# adc-power.net
KiCad netlist of a schematic drawn in Altium Designer
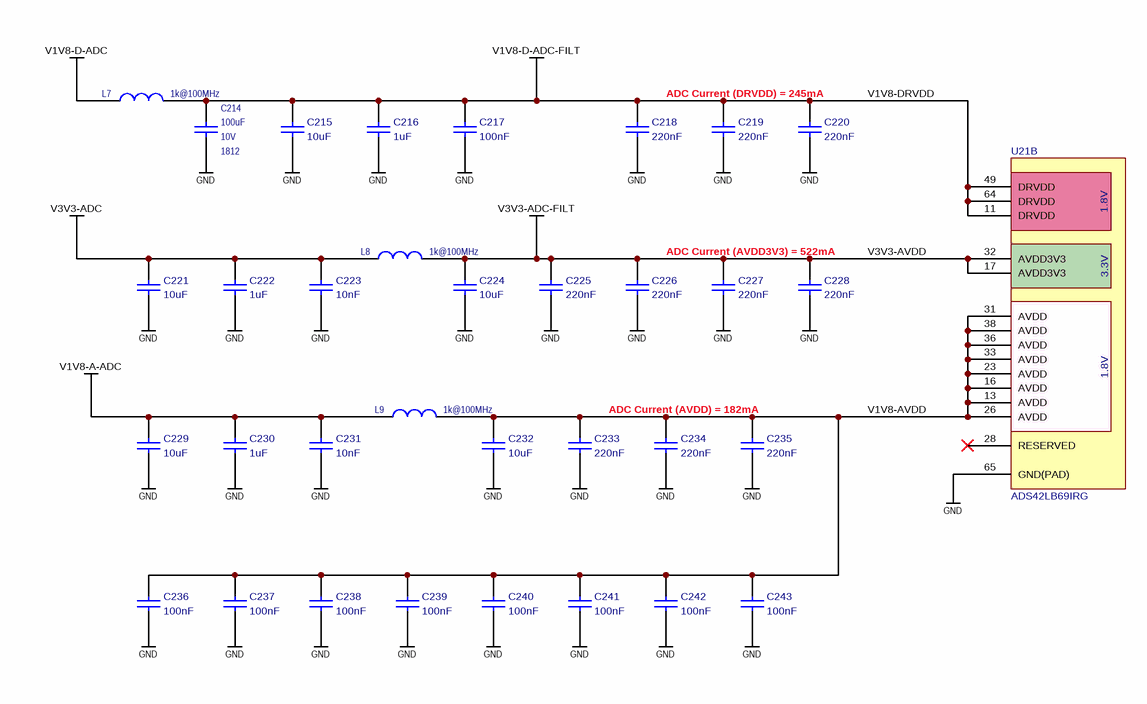
[diagram p0: adc-power.SchDoc]

(export (version "E")
  (design (tool "Eeschema 10.0.6"))
  (components
    (comp (ref "C214")
      (value "100uF")
      (footprint "generic:CAPC450X320X360L20N")
      (description "Ceramic Capacitor 100uF ±20% 10V X5R 1812")
      (fields
        (field (name "MANUFACTURER") "TDK")
        (field (name "VOLTAGE") "10V")
        (field (name "PACKAGE") "1812")
        (field (name "TOLERANCE") "±20%")
      )
      (libsource (lib "generic") (part "CAP 0603"))
    )
    (comp (ref "C215")
      (value "10uF")
      (footprint "CAPC200X125X145L45N")
      (description "Ceramic Capacitor 10uF ±10% 16V X7R 0805")
      (fields (field (name "MANUFACTURER") "Samsung") (field (name "TOLERANCE") "±10%"))
      (libsource (lib "capacitors") (part "CAP"))
    )
    (comp (ref "C216")
      (value "1uF")
      (footprint "CAPC200X125X145L45N")
      (description "Ceramic Capacitor 1uF ±10% 25V X7R 0805")
      (fields (field (name "MANUFACTURER") "Taiyo Yuden") (field (name "TOLERANCE") "±10%"))
      (libsource (lib "capacitors") (part "CAP"))
    )
    (comp (ref "C217")
      (value "100nF")
      (footprint "CAPC100X50X55L25N")
      (description "Ceramic Capacitor 100nF ±10% 25V X7R 0402")
      (fields (field (name "MANUFACTURER") "Yageo") (field (name "TOLERANCE") "±10%"))
      (libsource (lib "capacitors") (part "CAP"))
    )
    (comp (ref "C218")
      (value "220nF")
      (footprint "CAPC100X50X55L25N")
      (description "Ceramic Capacitor 220nF ±10% 25V X7R 0402")
      (fields (field (name "MANUFACTURER") "TDK") (field (name "TOLERANCE") "±10%"))
      (libsource (lib "capacitors") (part "CAP"))
    )
    (comp (ref "C219")
      (value "220nF")
      (footprint "CAPC100X50X55L25N")
      (description "Ceramic Capacitor 220nF ±10% 25V X7R 0402")
      (fields (field (name "MANUFACTURER") "TDK") (field (name "TOLERANCE") "±10%"))
      (libsource (lib "capacitors") (part "CAP"))
    )
    (comp (ref "C220")
      (value "220nF")
      (footprint "CAPC100X50X55L25N")
      (description "Ceramic Capacitor 220nF ±10% 25V X7R 0402")
      (fields (field (name "MANUFACTURER") "TDK") (field (name "TOLERANCE") "±10%"))
      (libsource (lib "capacitors") (part "CAP"))
    )
    (comp (ref "C221")
      (value "10uF")
      (footprint "CAPC200X125X145L45N")
      (description "Ceramic Capacitor 10uF ±10% 16V X7R 0805")
      (fields (field (name "MANUFACTURER") "Samsung") (field (name "TOLERANCE") "±10%"))
      (libsource (lib "capacitors") (part "CAP"))
    )
    (comp (ref "C222")
      (value "1uF")
      (footprint "CAPC200X125X145L45N")
      (description "Ceramic Capacitor 1uF ±10% 25V X7R 0805")
      (fields (field (name "MANUFACTURER") "Taiyo Yuden") (field (name "TOLERANCE") "±10%"))
      (libsource (lib "capacitors") (part "CAP"))
    )
    (comp (ref "C223")
      (value "10nF")
      (footprint "generic:CAPC100X50X55L25N")
      (description "Ceramic Capacitor 10nF ±10% 50V X7R 0402")
      (fields (field (name "MANUFACTURER") "Murata") (field (name "TOLERANCE") "±10%"))
      (libsource (lib "capacitors") (part "CAP"))
    )
    (comp (ref "C224")
      (value "10uF")
      (footprint "CAPC200X125X145L45N")
      (description "Ceramic Capacitor 10uF ±10% 16V X7R 0805")
      (fields (field (name "MANUFACTURER") "Samsung") (field (name "TOLERANCE") "±10%"))
      (libsource (lib "capacitors") (part "CAP"))
    )
    (comp (ref "C225")
      (value "220nF")
      (footprint "CAPC100X50X55L25N")
      (description "Ceramic Capacitor 220nF ±10% 25V X7R 0402")
      (fields (field (name "MANUFACTURER") "TDK") (field (name "TOLERANCE") "±10%"))
      (libsource (lib "capacitors") (part "CAP"))
    )
    (comp (ref "C226")
      (value "220nF")
      (footprint "CAPC100X50X55L25N")
      (description "Ceramic Capacitor 220nF ±10% 25V X7R 0402")
      (fields (field (name "MANUFACTURER") "TDK") (field (name "TOLERANCE") "±10%"))
      (libsource (lib "capacitors") (part "CAP"))
    )
    (comp (ref "C227")
      (value "220nF")
      (footprint "CAPC100X50X55L25N")
      (description "Ceramic Capacitor 220nF ±10% 25V X7R 0402")
      (fields (field (name "MANUFACTURER") "TDK") (field (name "TOLERANCE") "±10%"))
      (libsource (lib "capacitors") (part "CAP"))
    )
    (comp (ref "C228")
      (value "220nF")
      (footprint "CAPC100X50X55L25N")
      (description "Ceramic Capacitor 220nF ±10% 25V X7R 0402")
      (fields (field (name "MANUFACTURER") "TDK") (field (name "TOLERANCE") "±10%"))
      (libsource (lib "capacitors") (part "CAP"))
    )
    (comp (ref "C229")
      (value "10uF")
      (footprint "CAPC200X125X145L45N")
      (description "Ceramic Capacitor 10uF ±10% 16V X7R 0805")
      (fields (field (name "MANUFACTURER") "Samsung") (field (name "TOLERANCE") "±10%"))
      (libsource (lib "capacitors") (part "CAP"))
    )
    (comp (ref "C230")
      (value "1uF")
      (footprint "CAPC200X125X145L45N")
      (description "Ceramic Capacitor 1uF ±10% 25V X7R 0805")
      (fields (field (name "MANUFACTURER") "Taiyo Yuden") (field (name "TOLERANCE") "±10%"))
      (libsource (lib "capacitors") (part "CAP"))
    )
    (comp (ref "C231")
      (value "10nF")
      (footprint "generic:CAPC100X50X55L25N")
      (description "Ceramic Capacitor 10nF ±10% 50V X7R 0402")
      (fields (field (name "MANUFACTURER") "Murata") (field (name "TOLERANCE") "±10%"))
      (libsource (lib "capacitors") (part "CAP"))
    )
    (comp (ref "C232")
      (value "10uF")
      (footprint "CAPC200X125X145L45N")
      (description "Ceramic Capacitor 10uF ±10% 16V X7R 0805")
      (fields (field (name "MANUFACTURER") "Samsung") (field (name "TOLERANCE") "±10%"))
      (libsource (lib "capacitors") (part "CAP"))
    )
    (comp (ref "C233")
      (value "220nF")
      (footprint "CAPC100X50X55L25N")
      (description "Ceramic Capacitor 220nF ±10% 25V X7R 0402")
      (fields (field (name "MANUFACTURER") "TDK") (field (name "TOLERANCE") "±10%"))
      (libsource (lib "capacitors") (part "CAP"))
    )
    (comp (ref "C234")
      (value "220nF")
      (footprint "CAPC100X50X55L25N")
      (description "Ceramic Capacitor 220nF ±10% 25V X7R 0402")
      (fields (field (name "MANUFACTURER") "TDK") (field (name "TOLERANCE") "±10%"))
      (libsource (lib "capacitors") (part "CAP"))
    )
    (comp (ref "C235")
      (value "220nF")
      (footprint "CAPC100X50X55L25N")
      (description "Ceramic Capacitor 220nF ±10% 25V X7R 0402")
      (fields (field (name "MANUFACTURER") "TDK") (field (name "TOLERANCE") "±10%"))
      (libsource (lib "capacitors") (part "CAP"))
    )
    (comp (ref "C236")
      (value "100nF")
      (footprint "CAPC100X50X55L25N")
      (description "Ceramic Capacitor 100nF ±10% 25V X7R 0402")
      (fields (field (name "MANUFACTURER") "Yageo") (field (name "TOLERANCE") "±10%"))
      (libsource (lib "capacitors") (part "CAP"))
    )
    (comp (ref "C237")
      (value "100nF")
      (footprint "CAPC100X50X55L25N")
      (description "Ceramic Capacitor 100nF ±10% 25V X7R 0402")
      (fields (field (name "MANUFACTURER") "Yageo") (field (name "TOLERANCE") "±10%"))
      (libsource (lib "capacitors") (part "CAP"))
    )
    (comp (ref "C238")
      (value "100nF")
      (footprint "CAPC100X50X55L25N")
      (description "Ceramic Capacitor 100nF ±10% 25V X7R 0402")
      (fields (field (name "MANUFACTURER") "Yageo") (field (name "TOLERANCE") "±10%"))
      (libsource (lib "capacitors") (part "CAP"))
    )
    (comp (ref "C239")
      (value "100nF")
      (footprint "CAPC100X50X55L25N")
      (description "Ceramic Capacitor 100nF ±10% 25V X7R 0402")
      (fields (field (name "MANUFACTURER") "Yageo") (field (name "TOLERANCE") "±10%"))
      (libsource (lib "capacitors") (part "CAP"))
    )
    (comp (ref "C240")
      (value "100nF")
      (footprint "CAPC100X50X55L25N")
      (description "Ceramic Capacitor 100nF ±10% 25V X7R 0402")
      (fields (field (name "MANUFACTURER") "Yageo") (field (name "TOLERANCE") "±10%"))
      (libsource (lib "capacitors") (part "CAP"))
    )
    (comp (ref "C241")
      (value "100nF")
      (footprint "CAPC100X50X55L25N")
      (description "Ceramic Capacitor 100nF ±10% 25V X7R 0402")
      (fields (field (name "MANUFACTURER") "Yageo") (field (name "TOLERANCE") "±10%"))
      (libsource (lib "capacitors") (part "CAP"))
    )
    (comp (ref "C242")
      (value "100nF")
      (footprint "CAPC100X50X55L25N")
      (description "Ceramic Capacitor 100nF ±10% 25V X7R 0402")
      (fields (field (name "MANUFACTURER") "Yageo") (field (name "TOLERANCE") "±10%"))
      (libsource (lib "capacitors") (part "CAP"))
    )
    (comp (ref "C243")
      (value "100nF")
      (footprint "CAPC100X50X55L25N")
      (description "Ceramic Capacitor 100nF ±10% 25V X7R 0402")
      (fields (field (name "MANUFACTURER") "Yageo") (field (name "TOLERANCE") "±10%"))
      (libsource (lib "capacitors") (part "CAP"))
    )
    (comp (ref "L7")
      (value "1k@100MHz")
      (footprint "generic:1806")
      (description "Ferrite Bead 1k@100MHz 1.5A 1806")
      (fields (field (name "MANUFACTURER") "Murata") (field (name "Comment") "BLM41PG102SN1L"))
      (libsource (lib "*") (part "INDUCTANCE1"))
    )
    (comp (ref "L8")
      (value "1k@100MHz")
      (footprint "generic:1806")
      (description "Ferrite Bead 1k@100MHz 1.5A 1806")
      (fields (field (name "MANUFACTURER") "Murata") (field (name "Comment") "BLM41PG102SN1L"))
      (libsource (lib "*") (part "INDUCTANCE1"))
    )
    (comp (ref "L9")
      (value "1k@100MHz")
      (footprint "generic:1806")
      (description "Ferrite Bead 1k@100MHz 1.5A 1806")
      (fields (field (name "MANUFACTURER") "Murata") (field (name "Comment") "BLM41PG102SN1L"))
      (libsource (lib "*") (part "INDUCTANCE1"))
    )
    (comp (ref "U21")
      (value "ADS42LB69IRG")
      (footprint "S-PVQFN-N64")
      (description "Dual-Channel, 16-Bit, 250-MSPS Analog-to-Digital Converter")
      (fields (field (name "MANUFACTURER") "Texas Instruments"))
      (libsource (lib "ti") (part "ADS42LB69IRG"))
    )
  )
  (nets
    (net (code "1") (name "/V1V8-AVDD") (class "Default")
      (node (ref "C232") (pin "1") (pinfunction "1_1") (pintype "passive"))
      (node (ref "C233") (pin "1") (pinfunction "1_1") (pintype "passive"))
      (node (ref "C234") (pin "1") (pinfunction "1_1") (pintype "passive"))
      (node (ref "C235") (pin "1") (pinfunction "1_1") (pintype "passive"))
      (node (ref "C236") (pin "1") (pinfunction "1_1") (pintype "passive"))
      (node (ref "C237") (pin "1") (pinfunction "1_1") (pintype "passive"))
      (node (ref "C238") (pin "1") (pinfunction "1_1") (pintype "passive"))
      (node (ref "C239") (pin "1") (pinfunction "1_1") (pintype "passive"))
      (node (ref "C240") (pin "1") (pinfunction "1_1") (pintype "passive"))
      (node (ref "C241") (pin "1") (pinfunction "1_1") (pintype "passive"))
      (node (ref "C242") (pin "1") (pinfunction "1_1") (pintype "passive"))
      (node (ref "C243") (pin "1") (pinfunction "1_1") (pintype "passive"))
      (node (ref "L9") (pin "2") (pinfunction "2_2") (pintype "passive"))
      (node (ref "U21") (pin "13") (pinfunction "AVDD_13") (pintype "power_in"))
      (node (ref "U21") (pin "16") (pinfunction "AVDD_16") (pintype "power_in"))
      (node (ref "U21") (pin "23") (pinfunction "AVDD_23") (pintype "power_in"))
      (node (ref "U21") (pin "26") (pinfunction "AVDD_26") (pintype "power_in"))
      (node (ref "U21") (pin "31") (pinfunction "AVDD_31") (pintype "power_in"))
      (node (ref "U21") (pin "33") (pinfunction "AVDD_33") (pintype "power_in"))
      (node (ref "U21") (pin "36") (pinfunction "AVDD_36") (pintype "power_in"))
      (node (ref "U21") (pin "38") (pinfunction "AVDD_38") (pintype "power_in"))
    )
    (net (code "2") (name "GND") (class "Default")
      (node (ref "C214") (pin "1") (pinfunction "1_1") (pintype "passive"))
      (node (ref "C215") (pin "2") (pinfunction "2_2") (pintype "passive"))
      (node (ref "C216") (pin "2") (pinfunction "2_2") (pintype "passive"))
      (node (ref "C217") (pin "2") (pinfunction "2_2") (pintype "passive"))
      (node (ref "C218") (pin "2") (pinfunction "2_2") (pintype "passive"))
      (node (ref "C219") (pin "2") (pinfunction "2_2") (pintype "passive"))
      (node (ref "C220") (pin "2") (pinfunction "2_2") (pintype "passive"))
      (node (ref "C221") (pin "2") (pinfunction "2_2") (pintype "passive"))
      (node (ref "C222") (pin "2") (pinfunction "2_2") (pintype "passive"))
      (node (ref "C223") (pin "2") (pinfunction "2_2") (pintype "passive"))
      (node (ref "C224") (pin "2") (pinfunction "2_2") (pintype "passive"))
      (node (ref "C225") (pin "2") (pinfunction "2_2") (pintype "passive"))
      (node (ref "C226") (pin "2") (pinfunction "2_2") (pintype "passive"))
      (node (ref "C227") (pin "2") (pinfunction "2_2") (pintype "passive"))
      (node (ref "C228") (pin "2") (pinfunction "2_2") (pintype "passive"))
      (node (ref "C229") (pin "2") (pinfunction "2_2") (pintype "passive"))
      (node (ref "C230") (pin "2") (pinfunction "2_2") (pintype "passive"))
      (node (ref "C231") (pin "2") (pinfunction "2_2") (pintype "passive"))
      (node (ref "C232") (pin "2") (pinfunction "2_2") (pintype "passive"))
      (node (ref "C233") (pin "2") (pinfunction "2_2") (pintype "passive"))
      (node (ref "C234") (pin "2") (pinfunction "2_2") (pintype "passive"))
      (node (ref "C235") (pin "2") (pinfunction "2_2") (pintype "passive"))
      (node (ref "C236") (pin "2") (pinfunction "2_2") (pintype "passive"))
      (node (ref "C237") (pin "2") (pinfunction "2_2") (pintype "passive"))
      (node (ref "C238") (pin "2") (pinfunction "2_2") (pintype "passive"))
      (node (ref "C239") (pin "2") (pinfunction "2_2") (pintype "passive"))
      (node (ref "C240") (pin "2") (pinfunction "2_2") (pintype "passive"))
      (node (ref "C241") (pin "2") (pinfunction "2_2") (pintype "passive"))
      (node (ref "C242") (pin "2") (pinfunction "2_2") (pintype "passive"))
      (node (ref "C243") (pin "2") (pinfunction "2_2") (pintype "passive"))
      (node (ref "U21") (pin "65") (pinfunction "GND(PAD)_65") (pintype "power_in"))
    )
    (net (code "3") (name "V1V8-A-ADC") (class "Default")
      (node (ref "C229") (pin "1") (pinfunction "1_1") (pintype "passive"))
      (node (ref "C230") (pin "1") (pinfunction "1_1") (pintype "passive"))
      (node (ref "C231") (pin "1") (pinfunction "1_1") (pintype "passive"))
      (node (ref "L9") (pin "1") (pinfunction "1_1") (pintype "passive"))
    )
    (net (code "4") (name "V1V8-D-ADC") (class "Default")
      (node (ref "L7") (pin "1") (pinfunction "1_1") (pintype "passive"))
    )
    (net (code "5") (name "V1V8-D-ADC-FILT") (class "Default")
      (node (ref "C214") (pin "2") (pinfunction "2_2") (pintype "passive"))
      (node (ref "C215") (pin "1") (pinfunction "1_1") (pintype "passive"))
      (node (ref "C216") (pin "1") (pinfunction "1_1") (pintype "passive"))
      (node (ref "C217") (pin "1") (pinfunction "1_1") (pintype "passive"))
      (node (ref "C218") (pin "1") (pinfunction "1_1") (pintype "passive"))
      (node (ref "C219") (pin "1") (pinfunction "1_1") (pintype "passive"))
      (node (ref "C220") (pin "1") (pinfunction "1_1") (pintype "passive"))
      (node (ref "L7") (pin "2") (pinfunction "2_2") (pintype "passive"))
      (node (ref "U21") (pin "11") (pinfunction "DRVDD_11") (pintype "power_in"))
      (node (ref "U21") (pin "49") (pinfunction "DRVDD_49") (pintype "power_in"))
      (node (ref "U21") (pin "64") (pinfunction "DRVDD_64") (pintype "power_in"))
    )
    (net (code "6") (name "V3V3-ADC") (class "Default")
      (node (ref "C221") (pin "1") (pinfunction "1_1") (pintype "passive"))
      (node (ref "C222") (pin "1") (pinfunction "1_1") (pintype "passive"))
      (node (ref "C223") (pin "1") (pinfunction "1_1") (pintype "passive"))
      (node (ref "L8") (pin "1") (pinfunction "1_1") (pintype "passive"))
    )
    (net (code "7") (name "V3V3-ADC-FILT") (class "Default")
      (node (ref "C224") (pin "1") (pinfunction "1_1") (pintype "passive"))
      (node (ref "C225") (pin "1") (pinfunction "1_1") (pintype "passive"))
      (node (ref "C226") (pin "1") (pinfunction "1_1") (pintype "passive"))
      (node (ref "C227") (pin "1") (pinfunction "1_1") (pintype "passive"))
      (node (ref "C228") (pin "1") (pinfunction "1_1") (pintype "passive"))
      (node (ref "L8") (pin "2") (pinfunction "2_2") (pintype "passive"))
      (node (ref "U21") (pin "17") (pinfunction "AVDD3V3_17") (pintype "power_in"))
      (node (ref "U21") (pin "32") (pinfunction "AVDD3V3_32") (pintype "power_in"))
    )
    (net (code "8") (name "unconnected-(U21B-RESERVED-Pad28)") (class "Default")
      (node (ref "U21") (pin "28") (pinfunction "RESERVED_28") (pintype "passive+no_connect"))
    )
  )
)
